# Boost_v3.net
KiCad netlist of a schematic drawn in EAGLE
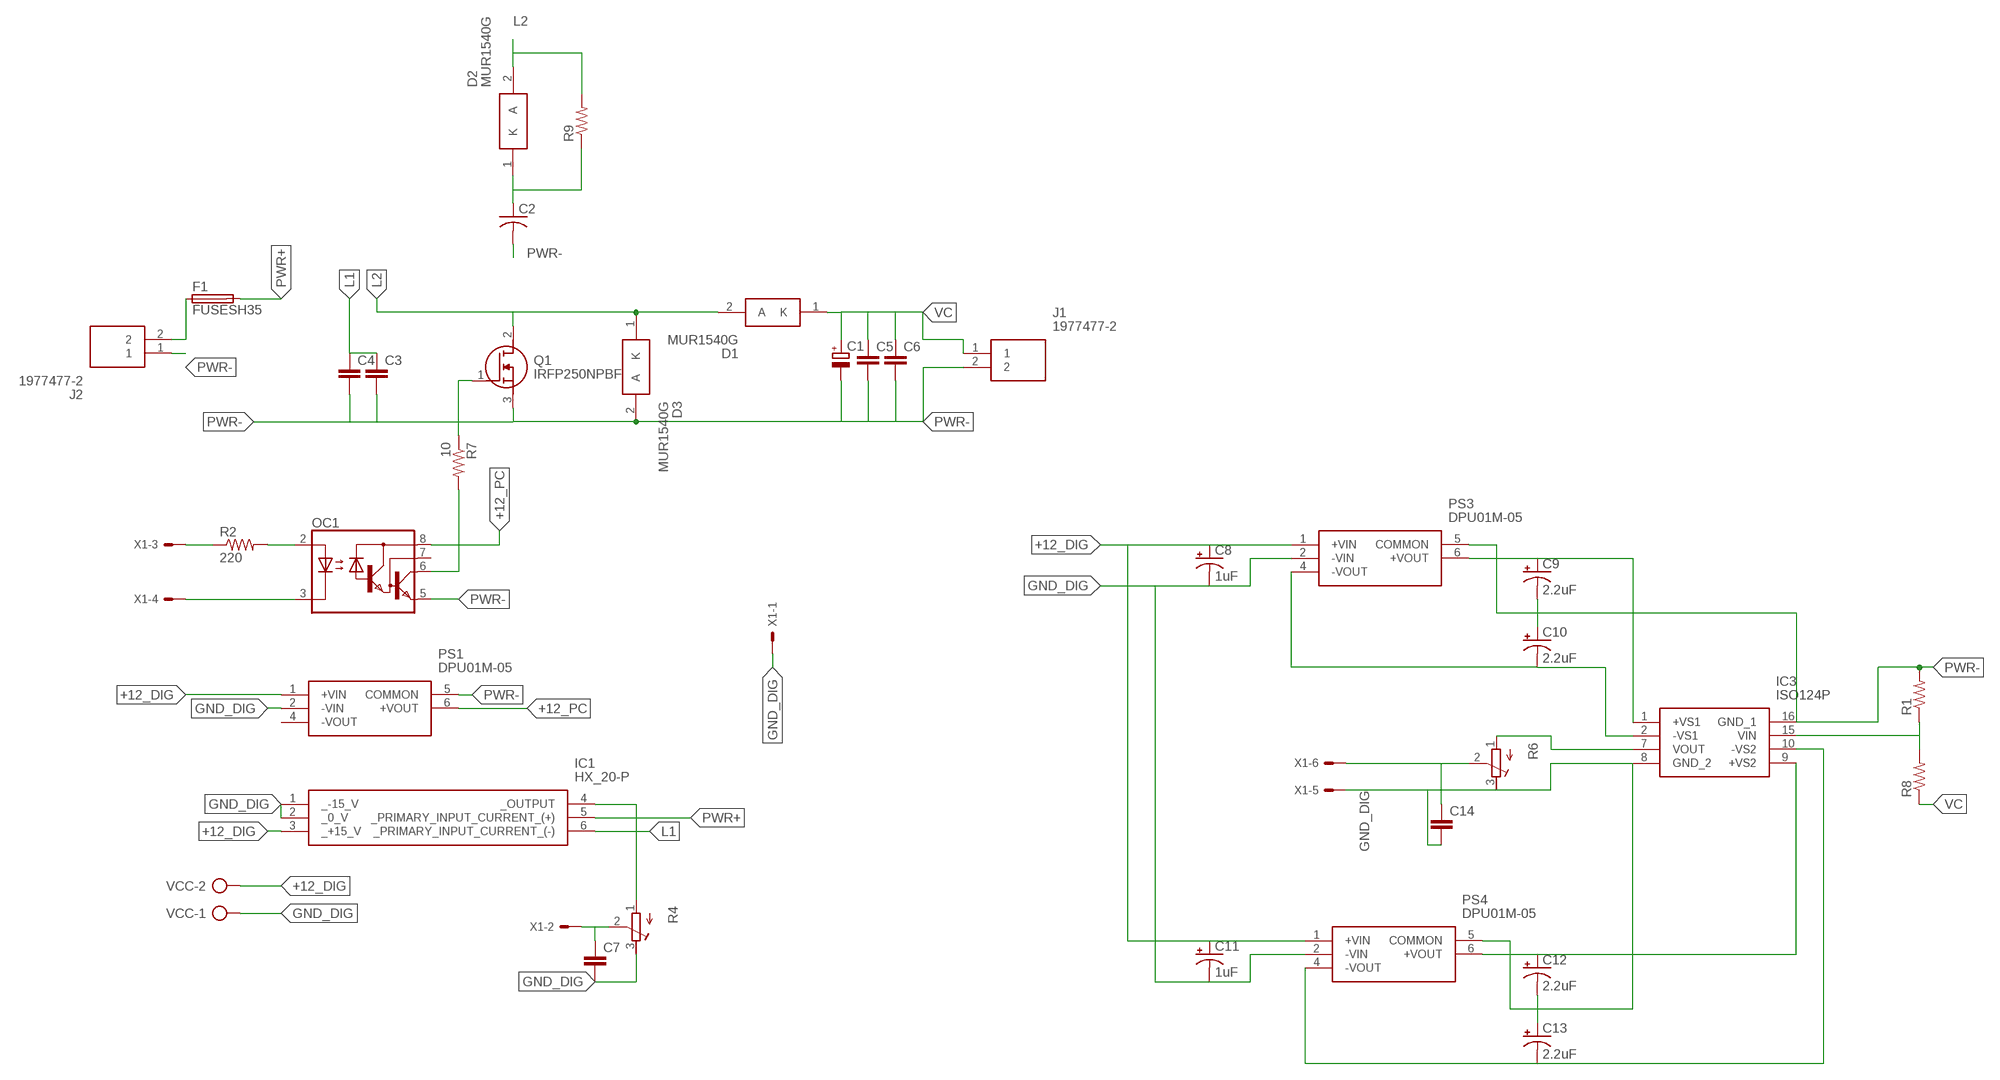
[diagram p0: schematic, sheet 1]

(export (version "E")
  (design (tool "Eeschema 10.0.6"))
  (components
    (comp (ref "C1")
      (value "CPOL-EUE10-35")
      (footprint "eagle-import:EB35D")
      (libsource (lib "eagle-import") (part "CPOL-EUE10-35"))
    )
    (comp (ref "C2")
      (value "C-US050-025X075")
      (footprint "eagle-import:C050-025X075")
      (libsource (lib "eagle-import") (part "C-US050-025X075"))
    )
    (comp (ref "C3")
      (value "C-EU050-030X075")
      (footprint "eagle-import:C050-030X075")
      (libsource (lib "eagle-import") (part "C-EU050-030X075"))
    )
    (comp (ref "C4")
      (value "C-EU050-030X075")
      (footprint "eagle-import:C050-030X075")
      (libsource (lib "eagle-import") (part "C-EU050-030X075"))
    )
    (comp (ref "C5")
      (value "C-EU050-030X075")
      (footprint "eagle-import:C050-030X075")
      (libsource (lib "eagle-import") (part "C-EU050-030X075"))
    )
    (comp (ref "C6")
      (value "C-EU050-030X075")
      (footprint "eagle-import:C050-030X075")
      (libsource (lib "eagle-import") (part "C-EU050-030X075"))
    )
    (comp (ref "C7")
      (value "C-EU050-030X075")
      (footprint "eagle-import:C050-030X075")
      (libsource (lib "eagle-import") (part "C-EU050-030X075"))
    )
    (comp (ref "C8")
      (value "1uF")
      (footprint "eagle-import:E2,5-5")
      (libsource (lib "eagle-import") (part "CPOL-USE2.5-5"))
    )
    (comp (ref "C9")
      (value "2.2uF")
      (footprint "eagle-import:E2,5-5")
      (libsource (lib "eagle-import") (part "CPOL-USE2.5-5"))
    )
    (comp (ref "C10")
      (value "2.2uF")
      (footprint "eagle-import:E2,5-5")
      (libsource (lib "eagle-import") (part "CPOL-USE2.5-5"))
    )
    (comp (ref "C11")
      (value "1uF")
      (footprint "eagle-import:E2,5-5")
      (libsource (lib "eagle-import") (part "CPOL-USE2.5-5"))
    )
    (comp (ref "C12")
      (value "2.2uF")
      (footprint "eagle-import:E2,5-5")
      (libsource (lib "eagle-import") (part "CPOL-USE2.5-5"))
    )
    (comp (ref "C13")
      (value "2.2uF")
      (footprint "eagle-import:E2,5-5")
      (libsource (lib "eagle-import") (part "CPOL-USE2.5-5"))
    )
    (comp (ref "C14")
      (value "C-EU050-030X075")
      (footprint "eagle-import:C050-030X075")
      (libsource (lib "eagle-import") (part "C-EU050-030X075"))
    )
    (comp (ref "D1")
      (value "MUR1540G")
      (footprint "eagle-import:TO533P482X997X1956-2P")
      (fields (field (name "MOUSER_PART_NUMBER") "863-MUR1540G") (field (name "RS_PART_NUMBER") "5449567P"))
      (libsource (lib "eagle-import") (part "MUR1540G"))
    )
    (comp (ref "D2")
      (value "MUR1540G")
      (footprint "eagle-import:TO533P482X997X1956-2P")
      (fields (field (name "MOUSER_PART_NUMBER") "863-MUR1540G") (field (name "RS_PART_NUMBER") "5449567P"))
      (libsource (lib "eagle-import") (part "MUR1540G"))
    )
    (comp (ref "D3")
      (value "MUR1540G")
      (footprint "eagle-import:TO533P482X997X1956-2P")
      (fields (field (name "MOUSER_PART_NUMBER") "863-MUR1540G") (field (name "RS_PART_NUMBER") "5449567P"))
      (libsource (lib "eagle-import") (part "MUR1540G"))
    )
    (comp (ref "F1")
      (value "FUSESH35")
      (footprint "eagle-import:SH25")
      (libsource (lib "eagle-import") (part "FUSESH35"))
    )
    (comp (ref "IC1")
      (value "HX_20-P")
      (footprint "eagle-import:HX20P")
      (fields (field (name "MANUFACTURER_PART_NUMBER") "HX 20-P"))
      (libsource (lib "eagle-import") (part "HX_20-P"))
    )
    (comp (ref "IC3")
      (value "ISO124P")
      (footprint "eagle-import:DIP254P762X533-8P")
      (fields (field (name "MOUSER_PART_NUMBER") "595-ISO124P") (field (name "RS_PART_NUMBER") "3008243P"))
      (libsource (lib "eagle-import") (part "ISO124P"))
    )
    (comp (ref "J1")
      (value "1977477-2")
      (footprint "eagle-import:SHDR2W165P0X825_1X2_1650X1370X")
      (fields (field (name "MOUSER_PART_NUMBER") "571-1977477-2"))
      (libsource (lib "eagle-import") (part "1977477-2"))
    )
    (comp (ref "J2")
      (value "1977477-2")
      (footprint "eagle-import:SHDR2W165P0X825_1X2_1650X1370X")
      (fields (field (name "MOUSER_PART_NUMBER") "571-1977477-2"))
      (libsource (lib "eagle-import") (part "1977477-2"))
    )
    (comp (ref "OC1")
      (value "6N138")
      (footprint "eagle-import:DIL08")
      (libsource (lib "eagle-import") (part "6N138"))
    )
    (comp (ref "PS1")
      (value "DPU01M-05")
      (footprint "eagle-import:DPU01M05")
      (fields (field (name "MOUSER_PART_NUMBER") "709-DPU01M-05"))
      (libsource (lib "eagle-import") (part "DPU01M-05"))
    )
    (comp (ref "PS3")
      (value "DPU01M-05")
      (footprint "eagle-import:DPU01M05")
      (fields (field (name "MOUSER_PART_NUMBER") "709-DPU01M-05"))
      (libsource (lib "eagle-import") (part "DPU01M-05"))
    )
    (comp (ref "PS4")
      (value "DPU01M-05")
      (footprint "eagle-import:DPU01M05")
      (fields (field (name "MOUSER_PART_NUMBER") "709-DPU01M-05"))
      (libsource (lib "eagle-import") (part "DPU01M-05"))
    )
    (comp (ref "Q1")
      (value "IRFP250NPBF")
      (footprint "eagle-import:TO545P530X1560X2460-3P")
      (fields (field (name "MOUSER_PART_NUMBER") "942-IRFP250NPBF"))
      (libsource (lib "eagle-import") (part "IRFP250NPBF"))
    )
    (comp (ref "R1")
      (value "R-US_VTA52")
      (footprint "eagle-import:VTA52")
      (libsource (lib "eagle-import") (part "R-US_VTA52"))
    )
    (comp (ref "R2")
      (value "220")
      (footprint "eagle-import:0207_10")
      (libsource (lib "eagle-import") (part "R-US_0207/10"))
    )
    (comp (ref "R4")
      (value "R-TRIMM64W")
      (footprint "eagle-import:RTRIM64W")
      (libsource (lib "eagle-import") (part "R-TRIMM64W"))
    )
    (comp (ref "R6")
      (value "R-TRIMM64W")
      (footprint "eagle-import:RTRIM64W")
      (libsource (lib "eagle-import") (part "R-TRIMM64W"))
    )
    (comp (ref "R7")
      (value "10")
      (footprint "eagle-import:0207_10")
      (libsource (lib "eagle-import") (part "R-US_0207/10"))
    )
    (comp (ref "R8")
      (value "R-US_VTA52")
      (footprint "eagle-import:VTA52")
      (libsource (lib "eagle-import") (part "R-US_VTA52"))
    )
    (comp (ref "R9")
      (value "R-US_VTA52")
      (footprint "eagle-import:VTA52")
      (libsource (lib "eagle-import") (part "R-US_VTA52"))
    )
    (comp (ref "VCC")
      (value "AK500/2")
      (footprint "eagle-import:AK500_2")
      (libsource (lib "eagle-import") (part "AK500/2"))
    )
    (comp (ref "X1")
      (value "22-23-2061")
      (footprint "eagle-import:22-23-2061")
      (fields (field (name "MF") "MOLEX"))
      (libsource (lib "eagle-import") (part "22-23-2061"))
    )
  )
  (nets
    (net (code "1") (name "+12_DIG") (class "Default")
      (node (ref "C11") (pin "+") (pinfunction "+_+") (pintype "passive"))
      (node (ref "C8") (pin "+") (pinfunction "+_+") (pintype "passive"))
      (node (ref "IC1") (pin "3") (pinfunction "_+15_V_3") (pintype "bidirectional"))
      (node (ref "PS1") (pin "1") (pinfunction "+VIN_1") (pintype "bidirectional"))
      (node (ref "PS3") (pin "1") (pinfunction "+VIN_1") (pintype "bidirectional"))
      (node (ref "PS4") (pin "1") (pinfunction "+VIN_1") (pintype "bidirectional"))
      (node (ref "VCC") (pin "2") (pinfunction "KL_2") (pintype "passive"))
    )
    (net (code "2") (name "+12_PC") (class "Default")
      (node (ref "OC1") (pin "8") (pinfunction "VCC_8") (pintype "passive"))
      (node (ref "PS1") (pin "6") (pinfunction "+VOUT_6") (pintype "bidirectional"))
    )
    (net (code "3") (name "GND_DIG") (class "Default")
      (node (ref "C11") (pin "-") (pinfunction "-_-") (pintype "passive"))
      (node (ref "C12") (pin "-") (pinfunction "-_-") (pintype "passive"))
      (node (ref "C13") (pin "+") (pinfunction "+_+") (pintype "passive"))
      (node (ref "C14") (pin "2") (pinfunction "2_2") (pintype "passive"))
      (node (ref "C7") (pin "2") (pinfunction "2_2") (pintype "passive"))
      (node (ref "C8") (pin "-") (pinfunction "-_-") (pintype "passive"))
      (node (ref "IC1") (pin "1") (pinfunction "_-15_V_1") (pintype "bidirectional"))
      (node (ref "IC1") (pin "2") (pinfunction "_0_V_2") (pintype "bidirectional"))
      (node (ref "IC3") (pin "8") (pinfunction "GND_2_8") (pintype "bidirectional"))
      (node (ref "PS1") (pin "2") (pinfunction "-VIN_2") (pintype "bidirectional"))
      (node (ref "PS3") (pin "2") (pinfunction "-VIN_2") (pintype "bidirectional"))
      (node (ref "PS4") (pin "2") (pinfunction "-VIN_2") (pintype "bidirectional"))
      (node (ref "PS4") (pin "5") (pinfunction "COMMON_5") (pintype "bidirectional"))
      (node (ref "R4") (pin "3") (pinfunction "E_3") (pintype "passive"))
      (node (ref "R6") (pin "3") (pinfunction "E_3") (pintype "passive"))
      (node (ref "VCC") (pin "1") (pinfunction "KL_1") (pintype "passive"))
      (node (ref "X1") (pin "1") (pinfunction "S_1") (pintype "passive"))
      (node (ref "X1") (pin "5") (pinfunction "S_5") (pintype "passive"))
    )
    (net (code "4") (name "L1") (class "Default")
      (node (ref "C3") (pin "1") (pinfunction "1_1") (pintype "passive"))
      (node (ref "C4") (pin "1") (pinfunction "1_1") (pintype "passive"))
      (node (ref "IC1") (pin "6") (pinfunction "_PRIMARY_INPUT_CURRENT_(-)_6") (pintype "bidirectional"))
    )
    (net (code "5") (name "L2") (class "Default")
      (node (ref "D1") (pin "2") (pinfunction "A_2") (pintype "bidirectional"))
      (node (ref "D2") (pin "2") (pinfunction "A_2") (pintype "bidirectional"))
      (node (ref "D3") (pin "1") (pinfunction "K_1") (pintype "bidirectional"))
      (node (ref "Q1") (pin "2") (pinfunction "D_2") (pintype "bidirectional"))
      (node (ref "R9") (pin "2") (pinfunction "2_2") (pintype "passive"))
    )
    (net (code "6") (name "Net-(D2-K)") (class "Default")
      (node (ref "C2") (pin "1") (pinfunction "1_1") (pintype "passive"))
      (node (ref "D2") (pin "1") (pinfunction "K_1") (pintype "bidirectional"))
      (node (ref "R9") (pin "1") (pinfunction "1_1") (pintype "passive"))
    )
    (net (code "7") (name "Net-(F1-Pad1)") (class "Default")
      (node (ref "F1") (pin "1") (pinfunction "1_1") (pintype "passive"))
      (node (ref "J2") (pin "2") (pinfunction "2_2") (pintype "bidirectional"))
    )
    (net (code "8") (name "Net-(IC1-_OUTPUT)") (class "Default")
      (node (ref "IC1") (pin "4") (pinfunction "_OUTPUT_4") (pintype "bidirectional"))
      (node (ref "R4") (pin "1") (pinfunction "A_1") (pintype "passive"))
    )
    (net (code "9") (name "Net-(IC3-+VS1)") (class "Default")
      (node (ref "C9") (pin "+") (pinfunction "+_+") (pintype "passive"))
      (node (ref "IC3") (pin "1") (pinfunction "+VS1_1") (pintype "bidirectional"))
      (node (ref "PS3") (pin "6") (pinfunction "+VOUT_6") (pintype "bidirectional"))
    )
    (net (code "10") (name "Net-(IC3-+VS2)") (class "Default")
      (node (ref "C12") (pin "+") (pinfunction "+_+") (pintype "passive"))
      (node (ref "IC3") (pin "9") (pinfunction "+VS2_9") (pintype "bidirectional"))
      (node (ref "PS4") (pin "6") (pinfunction "+VOUT_6") (pintype "bidirectional"))
    )
    (net (code "11") (name "Net-(IC3--VS1)") (class "Default")
      (node (ref "C10") (pin "-") (pinfunction "-_-") (pintype "passive"))
      (node (ref "IC3") (pin "2") (pinfunction "-VS1_2") (pintype "bidirectional"))
      (node (ref "PS3") (pin "4") (pinfunction "-VOUT_4") (pintype "bidirectional"))
    )
    (net (code "12") (name "Net-(IC3--VS2)") (class "Default")
      (node (ref "C13") (pin "-") (pinfunction "-_-") (pintype "passive"))
      (node (ref "IC3") (pin "10") (pinfunction "-VS2_10") (pintype "bidirectional"))
      (node (ref "PS4") (pin "4") (pinfunction "-VOUT_4") (pintype "bidirectional"))
    )
    (net (code "13") (name "Net-(IC3-VIN)") (class "Default")
      (node (ref "IC3") (pin "15") (pinfunction "VIN_15") (pintype "bidirectional"))
      (node (ref "R1") (pin "1") (pinfunction "1_1") (pintype "passive"))
      (node (ref "R8") (pin "2") (pinfunction "2_2") (pintype "passive"))
    )
    (net (code "14") (name "Net-(IC3-VOUT)") (class "Default")
      (node (ref "IC3") (pin "7") (pinfunction "VOUT_7") (pintype "bidirectional"))
      (node (ref "R6") (pin "1") (pinfunction "A_1") (pintype "passive"))
    )
    (net (code "15") (name "Net-(OC1-A)") (class "Default")
      (node (ref "OC1") (pin "2") (pinfunction "A_2") (pintype "passive"))
      (node (ref "R2") (pin "2") (pinfunction "2_2") (pintype "passive"))
    )
    (net (code "16") (name "Net-(OC1-C)") (class "Default")
      (node (ref "OC1") (pin "3") (pinfunction "C_3") (pintype "passive"))
      (node (ref "X1") (pin "4") (pinfunction "S_4") (pintype "passive"))
    )
    (net (code "17") (name "Net-(OC1-VO)") (class "Default")
      (node (ref "OC1") (pin "6") (pinfunction "VO_6") (pintype "passive"))
      (node (ref "R7") (pin "2") (pinfunction "2_2") (pintype "passive"))
    )
    (net (code "18") (name "Net-(Q1-G)") (class "Default")
      (node (ref "Q1") (pin "1") (pinfunction "G_1") (pintype "bidirectional"))
      (node (ref "R7") (pin "1") (pinfunction "1_1") (pintype "passive"))
    )
    (net (code "19") (name "Net-(R4-S)") (class "Default")
      (node (ref "C7") (pin "1") (pinfunction "1_1") (pintype "passive"))
      (node (ref "R4") (pin "2") (pinfunction "S_2") (pintype "passive"))
      (node (ref "X1") (pin "2") (pinfunction "S_2") (pintype "passive"))
    )
    (net (code "20") (name "Net-(R6-S)") (class "Default")
      (node (ref "C14") (pin "1") (pinfunction "1_1") (pintype "passive"))
      (node (ref "R6") (pin "2") (pinfunction "S_2") (pintype "passive"))
      (node (ref "X1") (pin "6") (pinfunction "S_6") (pintype "passive"))
    )
    (net (code "21") (name "Net-(X1C-S)") (class "Default")
      (node (ref "R2") (pin "1") (pinfunction "1_1") (pintype "passive"))
      (node (ref "X1") (pin "3") (pinfunction "S_3") (pintype "passive"))
    )
    (net (code "22") (name "PWR+") (class "Default")
      (node (ref "F1") (pin "2") (pinfunction "2_2") (pintype "passive"))
      (node (ref "IC1") (pin "5") (pinfunction "_PRIMARY_INPUT_CURRENT_(+)_5") (pintype "bidirectional"))
    )
    (net (code "23") (name "PWR-") (class "Default")
      (node (ref "C1") (pin "-") (pinfunction "-_-") (pintype "passive"))
      (node (ref "C10") (pin "+") (pinfunction "+_+") (pintype "passive"))
      (node (ref "C2") (pin "2") (pinfunction "2_2") (pintype "passive"))
      (node (ref "C3") (pin "2") (pinfunction "2_2") (pintype "passive"))
      (node (ref "C4") (pin "2") (pinfunction "2_2") (pintype "passive"))
      (node (ref "C5") (pin "2") (pinfunction "2_2") (pintype "passive"))
      (node (ref "C6") (pin "2") (pinfunction "2_2") (pintype "passive"))
      (node (ref "C9") (pin "-") (pinfunction "-_-") (pintype "passive"))
      (node (ref "D3") (pin "2") (pinfunction "A_2") (pintype "bidirectional"))
      (node (ref "IC3") (pin "16") (pinfunction "GND_1_16") (pintype "bidirectional"))
      (node (ref "J1") (pin "2") (pinfunction "2_2") (pintype "bidirectional"))
      (node (ref "J2") (pin "1") (pinfunction "1_1") (pintype "bidirectional"))
      (node (ref "OC1") (pin "5") (pinfunction "GND_5") (pintype "passive"))
      (node (ref "PS1") (pin "5") (pinfunction "COMMON_5") (pintype "bidirectional"))
      (node (ref "PS3") (pin "5") (pinfunction "COMMON_5") (pintype "bidirectional"))
      (node (ref "Q1") (pin "3") (pinfunction "S_3") (pintype "bidirectional"))
      (node (ref "R1") (pin "2") (pinfunction "2_2") (pintype "passive"))
    )
    (net (code "24") (name "VC") (class "Default")
      (node (ref "C1") (pin "+") (pinfunction "+_+") (pintype "passive"))
      (node (ref "C5") (pin "1") (pinfunction "1_1") (pintype "passive"))
      (node (ref "C6") (pin "1") (pinfunction "1_1") (pintype "passive"))
      (node (ref "D1") (pin "1") (pinfunction "K_1") (pintype "bidirectional"))
      (node (ref "J1") (pin "1") (pinfunction "1_1") (pintype "bidirectional"))
      (node (ref "R8") (pin "1") (pinfunction "1_1") (pintype "passive"))
    )
    (net (code "25") (name "unconnected-(OC1-VB-Pad7)") (class "Default")
      (node (ref "OC1") (pin "7") (pinfunction "VB_7") (pintype "passive"))
    )
    (net (code "26") (name "unconnected-(PS1--VOUT-Pad4)") (class "Default")
      (node (ref "PS1") (pin "4") (pinfunction "-VOUT_4") (pintype "bidirectional"))
    )
  )
)
